# AIM2_-_GPS_REVB.net
KiCad netlist of a schematic drawn in Altium Designer
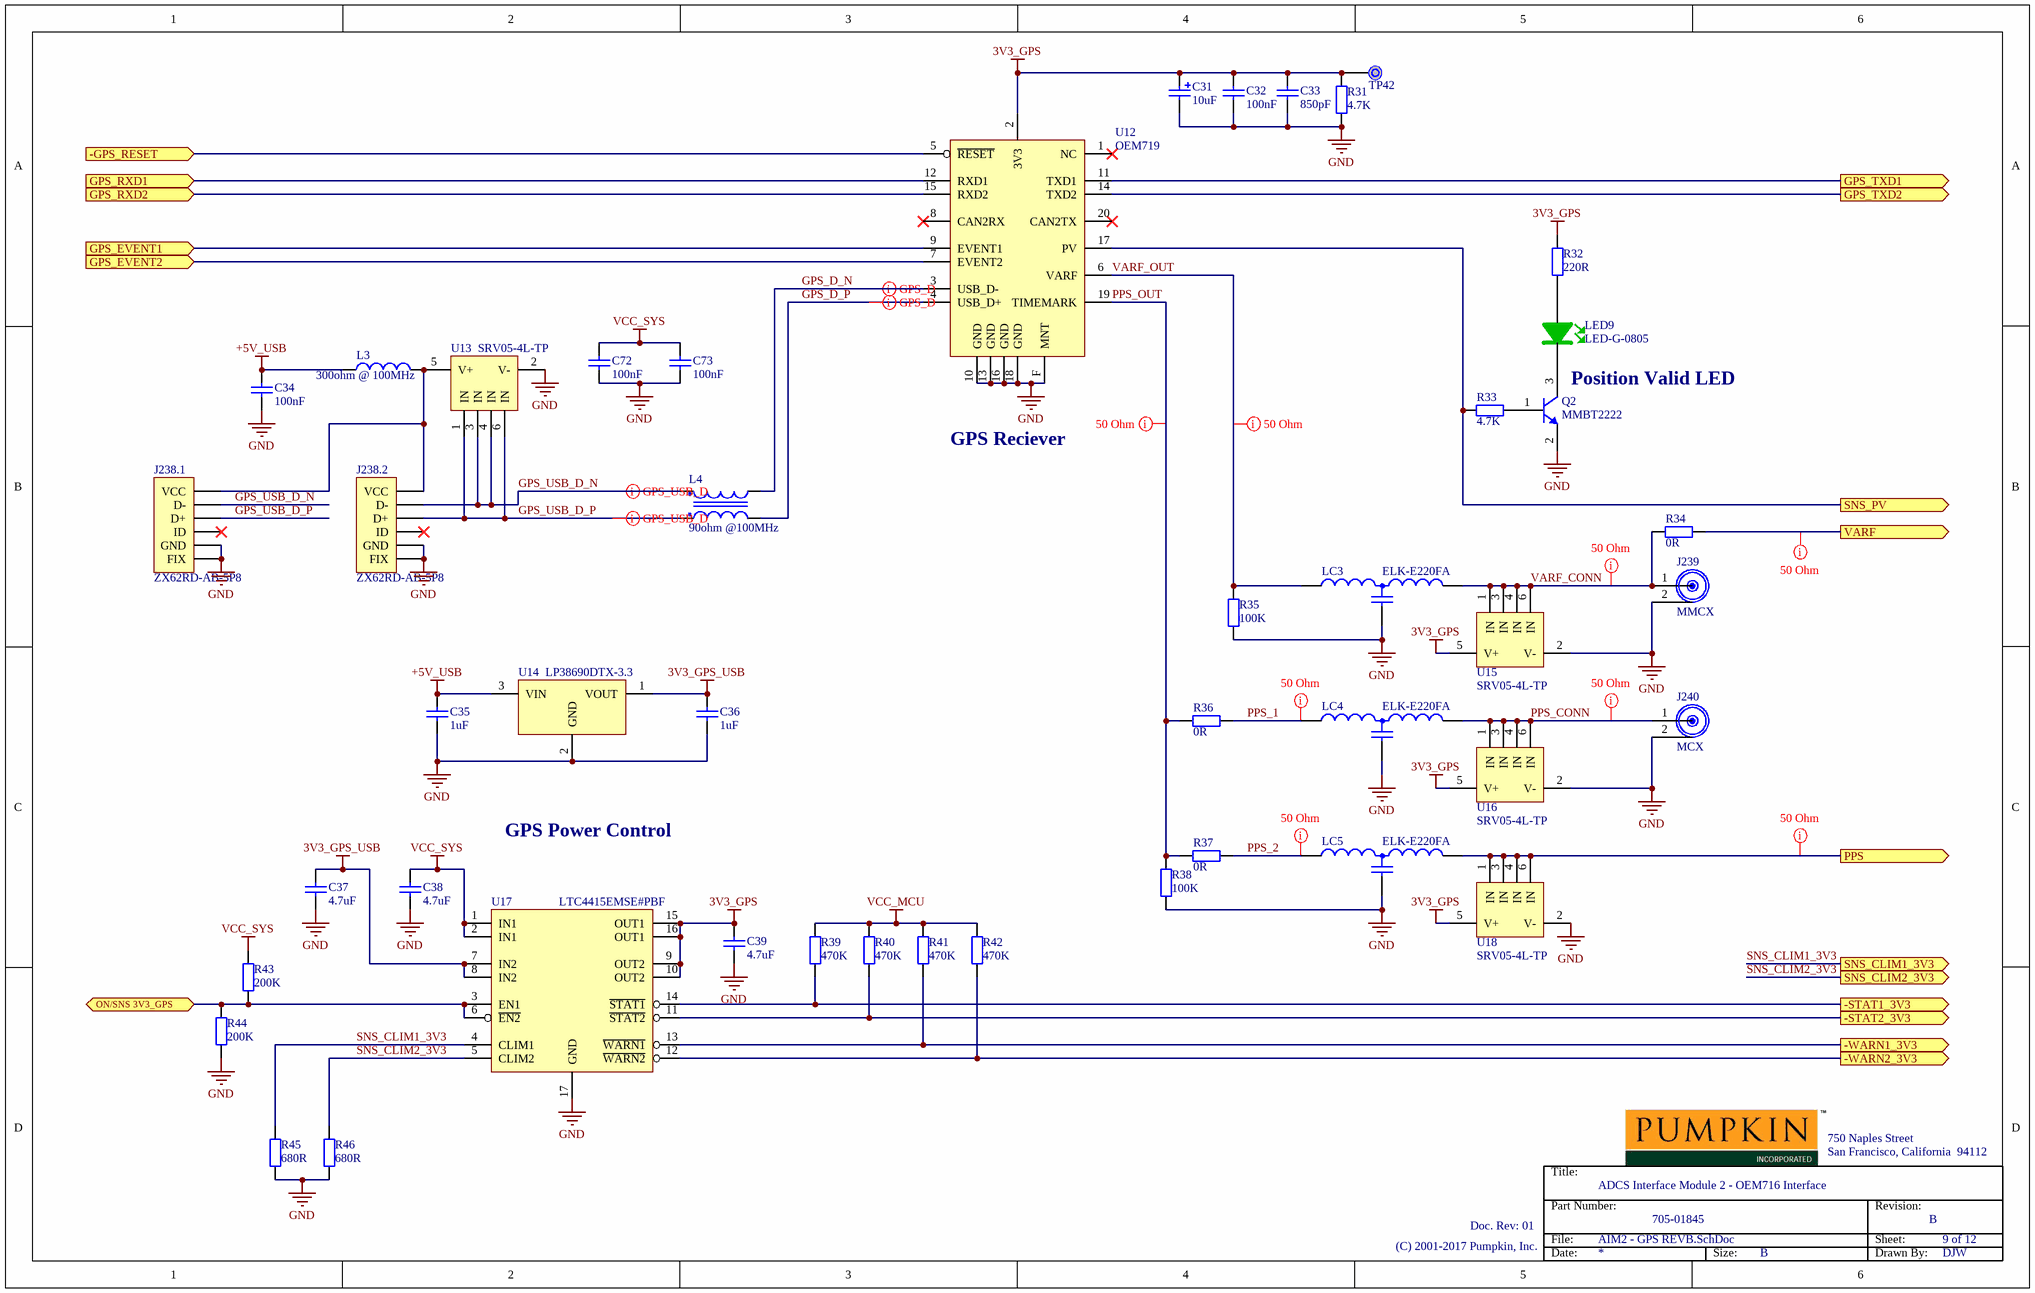
[diagram p0: AIM2 - GPS REVB.SchDoc]

(export (version "E")
  (design (tool "Eeschema 10.0.6"))
  (components
    (comp (ref "C31")
      (value "10uF")
      (footprint "6032 POLAR CAP")
      (description "Capacitor 10uF 6032 TANT 16V 10%")
      (libsource (lib "Supernova passives") (part "Capacitor 10uF 6032 Tantalum"))
    )
    (comp (ref "C32")
      (value "100nF")
      (footprint "0603 CAP")
      (description "Capacitor 100nF 0603 X7R 50V 5%")
      (libsource (lib "Supernova passives") (part "Capacitor 100nF 0603"))
    )
    (comp (ref "C33")
      (value "850pF")
      (footprint "0603 CAP")
      (description "Capacitor 850pF 0603 100V")
      (libsource (lib "Supernova passives") (part "Capacitor 850pF 0603"))
    )
    (comp (ref "C34")
      (value "100nF")
      (footprint "0603 CAP")
      (description "Capacitor 100nF 0603 X7R 50V 5%")
      (libsource (lib "Supernova passives") (part "Capacitor 100nF 0603"))
    )
    (comp (ref "C35")
      (value "1uF")
      (footprint "0805 CAP")
      (description "Capacitor 1uF 0805 X7R 25V 10%")
      (libsource (lib "Supernova passives") (part "Capacitor 1uF 0805"))
    )
    (comp (ref "C36")
      (value "1uF")
      (footprint "0805 CAP")
      (description "Capacitor 1uF 0805 X7R 25V 10%")
      (libsource (lib "Supernova passives") (part "Capacitor 1uF 0805"))
    )
    (comp (ref "C37")
      (value "4.7uF")
      (footprint "0805 CAP")
      (description "Capacitor 4.7uF 0805 X7R 35V 10%")
      (libsource (lib "Supernova passives") (part "Capacitor 4.7uF 0805"))
    )
    (comp (ref "C38")
      (value "4.7uF")
      (footprint "0805 CAP")
      (description "Capacitor 4.7uF 0805 X7R 35V 10%")
      (libsource (lib "Supernova passives") (part "Capacitor 4.7uF 0805"))
    )
    (comp (ref "C39")
      (value "4.7uF")
      (footprint "0805 CAP")
      (description "Capacitor 4.7uF 0805 X7R 35V 10%")
      (libsource (lib "Supernova passives") (part "Capacitor 4.7uF 0805"))
    )
    (comp (ref "C72")
      (value "100nF")
      (footprint "0603 CAP")
      (description "Capacitor 100nF 0603 X7R 50V 5%")
      (libsource (lib "Supernova passives") (part "Capacitor 100nF 0603"))
    )
    (comp (ref "C73")
      (value "100nF")
      (footprint "0603 CAP")
      (description "Capacitor 100nF 0603 X7R 50V 5%")
      (libsource (lib "Supernova passives") (part "Capacitor 100nF 0603"))
    )
    (comp (ref "J238.1")
      (value "ZX62RD-AB-5P8")
      (footprint "SM$5C$ZX62RD-AB-5P8")
      (description "Header USB Micro AB")
      (libsource (lib "Supernova") (part "ZX62RD-AB-5P8"))
    )
    (comp (ref "J238.2")
      (value "ZX62RD-AB-5P8")
      (footprint "SM$5C$ZX62RD-AB-5P8")
      (description "Header USB Micro AB")
      (libsource (lib "Supernova") (part "ZX62RD-AB-5P8"))
    )
    (comp (ref "J239")
      (value "MMCX")
      (footprint "mmcx")
      (description "Header MMCX Through-hole vertical")
      (libsource (lib "Supernova") (part "MMCX"))
    )
    (comp (ref "J240")
      (value "MCX")
      (footprint "MCX")
      (description "Header MCX Through-hole vertical")
      (libsource (lib "Supernova") (part "MCX"))
    )
    (comp (ref "L3")
      (value "300ohm @ 100MHz")
      (footprint "0603 IND")
      (description "Ferrite Bead 300ohm @ 100MHz")
      (libsource (lib "Supernova passives") (part "Ferrite Bead 300ohm @ 100MHz"))
    )
    (comp (ref "L4")
      (value "90ohm @100MHz")
      (footprint "DFN250P320X200-4N")
      (description "Choke Common-mode 90ohm @ 100MHz")
      (libsource (lib "Supernova passives") (part "Choke 90ohm @ 100MHz"))
    )
    (comp (ref "LC3")
      (value "ELK-E220FA")
      (footprint "ELK")
      (description "Filter LC 100MHz")
      (libsource (lib "Supernova passives") (part "LC Filter"))
    )
    (comp (ref "LC4")
      (value "ELK-E220FA")
      (footprint "ELK")
      (description "Filter LC 100MHz")
      (libsource (lib "Supernova passives") (part "LC Filter"))
    )
    (comp (ref "LC5")
      (value "ELK-E220FA")
      (footprint "ELK")
      (description "Filter LC 100MHz")
      (libsource (lib "Supernova passives") (part "LC Filter"))
    )
    (comp (ref "LED9")
      (value "LED-G-0805")
      (footprint "0805 LED-GREEN")
      (description "LED Green 0805")
      (libsource (lib "Supernova passives") (part "LED GREEN 0805"))
    )
    (comp (ref "Q2")
      (value "MMBT2222")
      (footprint "SOT23-3")
      (description "Transistor NPN")
      (libsource (lib "Supernova") (part "MMBT2222ALT1GOSCT-ND"))
    )
    (comp (ref "R31")
      (value "4.7K")
      (footprint "0805 RES")
      (description "Resistor 4.7K 0805 0.125W 1%")
      (libsource (lib "") (part "Resistor 4K7 0805_1"))
    )
    (comp (ref "R32")
      (value "220R")
      (footprint "0805 RES")
      (description "Resistor 220R 0805 0.125W 1%")
      (libsource (lib "Supernova passives") (part "Resistor 220R 0805"))
    )
    (comp (ref "R33")
      (value "4.7K")
      (footprint "0805 RES")
      (description "Resistor 4.7K 0805 0.125W 1%")
      (libsource (lib "Supernova passives") (part "Resistor 4K7 0805"))
    )
    (comp (ref "R34")
      (value "0R")
      (footprint "0805 RES")
      (description "Resistor 0R 0805 0.125W")
      (libsource (lib "Supernova passives") (part "Resistor 0R 0805"))
    )
    (comp (ref "R35")
      (value "100K")
      (footprint "0805 RES")
      (description "Resistor 100K 0805 0.5W 1%")
      (libsource (lib "Supernova passives") (part "Resistor 100K 0805"))
    )
    (comp (ref "R36")
      (value "0R")
      (footprint "0805 RES")
      (description "Resistor 0R 0805 0.125W")
      (libsource (lib "Supernova passives") (part "Resistor 0R 0805"))
    )
    (comp (ref "R37")
      (value "0R")
      (footprint "0805 RES")
      (description "Resistor 0R 0805 0.125W")
      (libsource (lib "Supernova passives") (part "Resistor 0R 0805"))
    )
    (comp (ref "R38")
      (value "100K")
      (footprint "0805 RES")
      (description "Resistor 100K 0805 0.5W 1%")
      (libsource (lib "Supernova passives") (part "Resistor 100K 0805"))
    )
    (comp (ref "R39")
      (value "470K")
      (footprint "0805 RES")
      (description "Resistor 470K 0805 0.125W 0.1%")
      (libsource (lib "Supernova passives") (part "Resistor 470K 0805"))
    )
    (comp (ref "R40")
      (value "470K")
      (footprint "0805 RES")
      (description "Resistor 470K 0805 0.125W 0.1%")
      (libsource (lib "Supernova passives") (part "Resistor 470K 0805"))
    )
    (comp (ref "R41")
      (value "470K")
      (footprint "0805 RES")
      (description "Resistor 470K 0805 0.125W 0.1%")
      (libsource (lib "Supernova passives") (part "Resistor 470K 0805"))
    )
    (comp (ref "R42")
      (value "470K")
      (footprint "0805 RES")
      (description "Resistor 470K 0805 0.125W 0.1%")
      (libsource (lib "Supernova passives") (part "Resistor 470K 0805"))
    )
    (comp (ref "R43")
      (value "200K")
      (footprint "0805 RES")
      (description "Resistor 200K 0805 0.125W 1%")
      (libsource (lib "Supernova passives") (part "Resistor 200K 0805"))
    )
    (comp (ref "R44")
      (value "200K")
      (footprint "0805 RES")
      (description "Resistor 200K 0805 0.125W 1%")
      (libsource (lib "Supernova passives") (part "Resistor 200K 0805"))
    )
    (comp (ref "R45")
      (value "680R")
      (footprint "0805 RES")
      (description "Resistor 470K 0805 0.125W 1%")
      (libsource (lib "Supernova passives") (part "Resistor 680R 0805"))
    )
    (comp (ref "R46")
      (value "680R")
      (footprint "0805 RES")
      (description "Resistor 470K 0805 0.125W 1%")
      (libsource (lib "Supernova passives") (part "Resistor 680R 0805"))
    )
    (comp (ref "TP42")
      (value "Testpoint")
      (footprint "Testpoint")
      (libsource (lib "Supernova") (part "Testpoint"))
    )
    (comp (ref "U12")
      (value "OEM719")
      (footprint "OEM719")
      (description "GPS Reciever")
      (libsource (lib "Supernova") (part "OEM719"))
    )
    (comp (ref "U13")
      (value "SRV05-4L-TP")
      (footprint "SOT23-6")
      (description "IC ESD protection 4 input")
      (libsource (lib "") (part "SRV05-4L-TP_1"))
    )
    (comp (ref "U14")
      (value "LP38690DTX-3.3")
      (footprint "DPAK")
      (description "Regulator 3.3V LDO")
      (libsource (lib "Supernova") (part "LP38690DTX-3.3"))
    )
    (comp (ref "U15")
      (value "SRV05-4L-TP")
      (footprint "SOT23-6")
      (description "IC ESD protection 4 input")
      (libsource (lib "Supernova") (part "SRV05-4L-TP"))
    )
    (comp (ref "U16")
      (value "SRV05-4L-TP")
      (footprint "SOT23-6")
      (description "IC ESD protection 4 input")
      (libsource (lib "Supernova") (part "SRV05-4L-TP"))
    )
    (comp (ref "U17")
      (value "LTC4415EMSE#PBF")
      (footprint "MSOP-16")
      (description "IC Driver Dual Idewal Diode")
      (libsource (lib "Supernova") (part "LTC4415"))
    )
    (comp (ref "U18")
      (value "SRV05-4L-TP")
      (footprint "SOT23-6")
      (description "IC ESD protection 4 input")
      (libsource (lib "Supernova") (part "SRV05-4L-TP"))
    )
  )
  (nets
    (net (code "1") (name "+5V_USB") (class "Default")
      (node (ref "C34") (pin "2") (pinfunction "2_2") (pintype "passive"))
      (node (ref "C35") (pin "2") (pinfunction "2_2") (pintype "passive"))
      (node (ref "L3") (pin "1") (pinfunction "1_1") (pintype "passive"))
      (node (ref "U14") (pin "3") (pinfunction "VIN_3") (pintype "passive"))
    )
    (net (code "2") (name "/-GPS_RESET") (class "Default")
      (node (ref "U12") (pin "5") (pinfunction "~{RESET}_5") (pintype "passive"))
    )
    (net (code "3") (name "/-STAT1_3V3") (class "Default")
      (node (ref "R39") (pin "1") (pinfunction "1_1") (pintype "passive"))
      (node (ref "U17") (pin "14") (pinfunction "~{STAT1}_14") (pintype "passive"))
    )
    (net (code "4") (name "/-STAT2_3V3") (class "Default")
      (node (ref "R40") (pin "1") (pinfunction "1_1") (pintype "passive"))
      (node (ref "U17") (pin "11") (pinfunction "~{STAT2}_11") (pintype "passive"))
    )
    (net (code "5") (name "/-WARN1_3V3") (class "Default")
      (node (ref "R41") (pin "1") (pinfunction "1_1") (pintype "passive"))
      (node (ref "U17") (pin "13") (pinfunction "~{WARN1}_13") (pintype "passive"))
    )
    (net (code "6") (name "/-WARN2_3V3") (class "Default")
      (node (ref "R42") (pin "1") (pinfunction "1_1") (pintype "passive"))
      (node (ref "U17") (pin "12") (pinfunction "~{WARN2}_12") (pintype "passive"))
    )
    (net (code "7") (name "/GPS_D_N") (class "Default")
      (node (ref "L4") (pin "2") (pinfunction "2_2") (pintype "passive"))
      (node (ref "U12") (pin "3") (pinfunction "USB_D-_3") (pintype "passive"))
    )
    (net (code "8") (name "/GPS_D_P") (class "Default")
      (node (ref "L4") (pin "3") (pinfunction "3_3") (pintype "passive"))
      (node (ref "U12") (pin "4") (pinfunction "USB_D+_4") (pintype "passive"))
    )
    (net (code "9") (name "/GPS_EVENT1") (class "Default")
      (node (ref "U12") (pin "9") (pinfunction "EVENT1_9") (pintype "passive"))
    )
    (net (code "10") (name "/GPS_EVENT2") (class "Default")
      (node (ref "U12") (pin "7") (pinfunction "EVENT2_7") (pintype "passive"))
    )
    (net (code "11") (name "/GPS_RXD1") (class "Default")
      (node (ref "U12") (pin "12") (pinfunction "RXD1_12") (pintype "passive"))
    )
    (net (code "12") (name "/GPS_RXD2") (class "Default")
      (node (ref "U12") (pin "15") (pinfunction "RXD2_15") (pintype "passive"))
    )
    (net (code "13") (name "/GPS_TXD1") (class "Default")
      (node (ref "U12") (pin "11") (pinfunction "TXD1_11") (pintype "passive"))
    )
    (net (code "14") (name "/GPS_TXD2") (class "Default")
      (node (ref "U12") (pin "14") (pinfunction "TXD2_14") (pintype "passive"))
    )
    (net (code "15") (name "/GPS_USB_D_N") (class "Default")
      (node (ref "J238.1") (pin "2") (pinfunction "D-_2") (pintype "passive"))
      (node (ref "J238.2") (pin "2") (pinfunction "D-_2") (pintype "passive"))
      (node (ref "L4") (pin "1") (pinfunction "1_1") (pintype "passive"))
      (node (ref "U13") (pin "3") (pinfunction "IN_3") (pintype "passive"))
      (node (ref "U13") (pin "4") (pinfunction "IN_4") (pintype "passive"))
    )
    (net (code "16") (name "/GPS_USB_D_P") (class "Default")
      (node (ref "J238.1") (pin "3") (pinfunction "D+_3") (pintype "passive"))
      (node (ref "J238.2") (pin "3") (pinfunction "D+_3") (pintype "passive"))
      (node (ref "L4") (pin "4") (pinfunction "4_4") (pintype "passive"))
      (node (ref "U13") (pin "1") (pinfunction "IN_1") (pintype "passive"))
      (node (ref "U13") (pin "6") (pinfunction "IN_6") (pintype "passive"))
    )
    (net (code "17") (name "/ON{slash}SNS 3V3_GPS") (class "Default")
      (node (ref "R43") (pin "1") (pinfunction "1_1") (pintype "passive"))
      (node (ref "R44") (pin "2") (pinfunction "2_2") (pintype "passive"))
      (node (ref "U17") (pin "3") (pinfunction "EN1_3") (pintype "passive"))
      (node (ref "U17") (pin "6") (pinfunction "~{EN2}_6") (pintype "passive"))
    )
    (net (code "18") (name "/PPS") (class "Default")
      (node (ref "LC5") (pin "3") (pinfunction "3_3") (pintype "passive"))
      (node (ref "U18") (pin "1") (pinfunction "IN_1") (pintype "passive"))
      (node (ref "U18") (pin "3") (pinfunction "IN_3") (pintype "passive"))
      (node (ref "U18") (pin "4") (pinfunction "IN_4") (pintype "passive"))
      (node (ref "U18") (pin "6") (pinfunction "IN_6") (pintype "passive"))
    )
    (net (code "19") (name "/PPS_1") (class "Default")
      (node (ref "LC4") (pin "1") (pinfunction "1_1") (pintype "passive"))
      (node (ref "R36") (pin "2") (pinfunction "2_2") (pintype "passive"))
    )
    (net (code "20") (name "/PPS_2") (class "Default")
      (node (ref "LC5") (pin "1") (pinfunction "1_1") (pintype "passive"))
      (node (ref "R37") (pin "2") (pinfunction "2_2") (pintype "passive"))
    )
    (net (code "21") (name "/PPS_CONN") (class "Default")
      (node (ref "J240") (pin "1") (pinfunction "7_1") (pintype "passive"))
      (node (ref "LC4") (pin "3") (pinfunction "3_3") (pintype "passive"))
      (node (ref "U16") (pin "1") (pinfunction "IN_1") (pintype "passive"))
      (node (ref "U16") (pin "3") (pinfunction "IN_3") (pintype "passive"))
      (node (ref "U16") (pin "4") (pinfunction "IN_4") (pintype "passive"))
      (node (ref "U16") (pin "6") (pinfunction "IN_6") (pintype "passive"))
    )
    (net (code "22") (name "/PPS_OUT") (class "Default")
      (node (ref "R36") (pin "1") (pinfunction "1_1") (pintype "passive"))
      (node (ref "R37") (pin "1") (pinfunction "1_1") (pintype "passive"))
      (node (ref "R38") (pin "2") (pinfunction "2_2") (pintype "passive"))
      (node (ref "U12") (pin "19") (pinfunction "TIMEMARK_19") (pintype "passive"))
    )
    (net (code "23") (name "/SNS_CLIM1_3V3") (class "Default")
      (node (ref "R45") (pin "2") (pinfunction "2_2") (pintype "passive"))
      (node (ref "U17") (pin "4") (pinfunction "CLIM1_4") (pintype "passive"))
    )
    (net (code "24") (name "/SNS_CLIM2_3V3") (class "Default")
      (node (ref "R46") (pin "2") (pinfunction "2_2") (pintype "passive"))
      (node (ref "U17") (pin "5") (pinfunction "CLIM2_5") (pintype "passive"))
    )
    (net (code "25") (name "/SNS_PV") (class "Default")
      (node (ref "R33") (pin "1") (pinfunction "1_1") (pintype "passive"))
      (node (ref "U12") (pin "17") (pinfunction "PV_17") (pintype "passive"))
    )
    (net (code "26") (name "/VARF") (class "Default")
      (node (ref "R34") (pin "2") (pinfunction "2_2") (pintype "passive"))
    )
    (net (code "27") (name "/VARF_CONN") (class "Default")
      (node (ref "J239") (pin "1") (pinfunction "7_1") (pintype "passive"))
      (node (ref "LC3") (pin "3") (pinfunction "3_3") (pintype "passive"))
      (node (ref "R34") (pin "1") (pinfunction "1_1") (pintype "passive"))
      (node (ref "U15") (pin "1") (pinfunction "IN_1") (pintype "passive"))
      (node (ref "U15") (pin "3") (pinfunction "IN_3") (pintype "passive"))
      (node (ref "U15") (pin "4") (pinfunction "IN_4") (pintype "passive"))
      (node (ref "U15") (pin "6") (pinfunction "IN_6") (pintype "passive"))
    )
    (net (code "28") (name "/VARF_OUT") (class "Default")
      (node (ref "LC3") (pin "1") (pinfunction "1_1") (pintype "passive"))
      (node (ref "R35") (pin "2") (pinfunction "2_2") (pintype "passive"))
      (node (ref "U12") (pin "6") (pinfunction "VARF_6") (pintype "passive"))
    )
    (net (code "29") (name "3V3_GPS") (class "Default")
      (node (ref "C31") (pin "1") (pinfunction "1_1") (pintype "passive"))
      (node (ref "C32") (pin "2") (pinfunction "2_2") (pintype "passive"))
      (node (ref "C33") (pin "2") (pinfunction "2_2") (pintype "passive"))
      (node (ref "C39") (pin "2") (pinfunction "2_2") (pintype "passive"))
      (node (ref "R31") (pin "2") (pinfunction "2_2") (pintype "passive"))
      (node (ref "R32") (pin "2") (pinfunction "2_2") (pintype "passive"))
      (node (ref "TP42") (pin "1") (pinfunction "1_1") (pintype "passive"))
      (node (ref "U12") (pin "2") (pinfunction "3V3_2") (pintype "passive"))
      (node (ref "U15") (pin "5") (pinfunction "V+_5") (pintype "passive"))
      (node (ref "U16") (pin "5") (pinfunction "V+_5") (pintype "passive"))
      (node (ref "U17") (pin "10") (pinfunction "OUT2_10") (pintype "passive"))
      (node (ref "U17") (pin "15") (pinfunction "OUT1_15") (pintype "passive"))
      (node (ref "U17") (pin "16") (pinfunction "OUT1_16") (pintype "passive"))
      (node (ref "U17") (pin "9") (pinfunction "OUT2_9") (pintype "passive"))
      (node (ref "U18") (pin "5") (pinfunction "V+_5") (pintype "passive"))
    )
    (net (code "30") (name "3V3_GPS_USB") (class "Default")
      (node (ref "C36") (pin "2") (pinfunction "2_2") (pintype "passive"))
      (node (ref "C37") (pin "2") (pinfunction "2_2") (pintype "passive"))
      (node (ref "U14") (pin "1") (pinfunction "VOUT_1") (pintype "passive"))
      (node (ref "U17") (pin "7") (pinfunction "IN2_7") (pintype "passive"))
      (node (ref "U17") (pin "8") (pinfunction "IN2_8") (pintype "passive"))
    )
    (net (code "31") (name "GND") (class "Default")
      (node (ref "C31") (pin "2") (pinfunction "2_2") (pintype "passive"))
      (node (ref "C32") (pin "1") (pinfunction "1_1") (pintype "passive"))
      (node (ref "C33") (pin "1") (pinfunction "1_1") (pintype "passive"))
      (node (ref "C34") (pin "1") (pinfunction "1_1") (pintype "passive"))
      (node (ref "C35") (pin "1") (pinfunction "1_1") (pintype "passive"))
      (node (ref "C36") (pin "1") (pinfunction "1_1") (pintype "passive"))
      (node (ref "C37") (pin "1") (pinfunction "1_1") (pintype "passive"))
      (node (ref "C38") (pin "1") (pinfunction "1_1") (pintype "passive"))
      (node (ref "C39") (pin "1") (pinfunction "1_1") (pintype "passive"))
      (node (ref "C72") (pin "1") (pinfunction "1_1") (pintype "passive"))
      (node (ref "C73") (pin "1") (pinfunction "1_1") (pintype "passive"))
      (node (ref "J238.1") (pin "5") (pinfunction "GND_5") (pintype "passive"))
      (node (ref "J238.1") (pin "F") (pinfunction "FIX_F") (pintype "passive"))
      (node (ref "J238.2") (pin "5") (pinfunction "GND_5") (pintype "passive"))
      (node (ref "J238.2") (pin "F") (pinfunction "FIX_F") (pintype "passive"))
      (node (ref "J239") (pin "2") (pinfunction "7_2") (pintype "passive"))
      (node (ref "J240") (pin "2") (pinfunction "7_2") (pintype "passive"))
      (node (ref "LC3") (pin "2") (pinfunction "2_2") (pintype "passive"))
      (node (ref "LC4") (pin "2") (pinfunction "2_2") (pintype "passive"))
      (node (ref "LC5") (pin "2") (pinfunction "2_2") (pintype "passive"))
      (node (ref "Q2") (pin "2") (pinfunction "E_2") (pintype "passive"))
      (node (ref "R31") (pin "1") (pinfunction "1_1") (pintype "passive"))
      (node (ref "R35") (pin "1") (pinfunction "1_1") (pintype "passive"))
      (node (ref "R38") (pin "1") (pinfunction "1_1") (pintype "passive"))
      (node (ref "R44") (pin "1") (pinfunction "1_1") (pintype "passive"))
      (node (ref "R45") (pin "1") (pinfunction "1_1") (pintype "passive"))
      (node (ref "R46") (pin "1") (pinfunction "1_1") (pintype "passive"))
      (node (ref "U12") (pin "10") (pinfunction "GND_10") (pintype "passive"))
      (node (ref "U12") (pin "13") (pinfunction "GND_13") (pintype "passive"))
      (node (ref "U12") (pin "16") (pinfunction "GND_16") (pintype "passive"))
      (node (ref "U12") (pin "18") (pinfunction "GND_18") (pintype "passive"))
      (node (ref "U12") (pin "F") (pinfunction "MNT_F") (pintype "passive"))
      (node (ref "U13") (pin "2") (pinfunction "V-_2") (pintype "passive"))
      (node (ref "U14") (pin "2") (pinfunction "GND_2") (pintype "passive"))
      (node (ref "U15") (pin "2") (pinfunction "V-_2") (pintype "passive"))
      (node (ref "U16") (pin "2") (pinfunction "V-_2") (pintype "passive"))
      (node (ref "U17") (pin "17") (pinfunction "GND_17") (pintype "passive"))
      (node (ref "U18") (pin "2") (pinfunction "V-_2") (pintype "passive"))
    )
    (net (code "32") (name "Net-(J238.1-VCC)") (class "Default")
      (node (ref "J238.1") (pin "1") (pinfunction "VCC_1") (pintype "passive"))
      (node (ref "J238.2") (pin "1") (pinfunction "VCC_1") (pintype "passive"))
      (node (ref "L3") (pin "2") (pinfunction "2_2") (pintype "passive"))
      (node (ref "U13") (pin "5") (pinfunction "V+_5") (pintype "passive"))
    )
    (net (code "33") (name "Net-(LED9-Pad2)") (class "Default")
      (node (ref "LED9") (pin "2") (pinfunction "2_2") (pintype "passive"))
      (node (ref "R32") (pin "1") (pinfunction "1_1") (pintype "passive"))
    )
    (net (code "34") (name "Net-(Q2-B)") (class "Default")
      (node (ref "Q2") (pin "1") (pinfunction "B_1") (pintype "passive"))
      (node (ref "R33") (pin "2") (pinfunction "2_2") (pintype "passive"))
    )
    (net (code "35") (name "Net-(Q2-C)") (class "Default")
      (node (ref "LED9") (pin "1") (pinfunction "1_1") (pintype "passive"))
      (node (ref "Q2") (pin "3") (pinfunction "C_3") (pintype "passive"))
    )
    (net (code "36") (name "VCC_MCU") (class "Default")
      (node (ref "R39") (pin "2") (pinfunction "2_2") (pintype "passive"))
      (node (ref "R40") (pin "2") (pinfunction "2_2") (pintype "passive"))
      (node (ref "R41") (pin "2") (pinfunction "2_2") (pintype "passive"))
      (node (ref "R42") (pin "2") (pinfunction "2_2") (pintype "passive"))
    )
    (net (code "37") (name "VCC_SYS") (class "Default")
      (node (ref "C38") (pin "2") (pinfunction "2_2") (pintype "passive"))
      (node (ref "C72") (pin "2") (pinfunction "2_2") (pintype "passive"))
      (node (ref "C73") (pin "2") (pinfunction "2_2") (pintype "passive"))
      (node (ref "R43") (pin "2") (pinfunction "2_2") (pintype "passive"))
      (node (ref "U17") (pin "1") (pinfunction "IN1_1") (pintype "passive"))
      (node (ref "U17") (pin "2") (pinfunction "IN1_2") (pintype "passive"))
    )
    (net (code "38") (name "unconnected-(J238.1-ID-Pad4)") (class "Default")
      (node (ref "J238.1") (pin "4") (pinfunction "ID_4") (pintype "passive+no_connect"))
    )
    (net (code "39") (name "unconnected-(J238.2-ID-Pad4)") (class "Default")
      (node (ref "J238.2") (pin "4") (pinfunction "ID_4") (pintype "passive+no_connect"))
    )
    (net (code "40") (name "unconnected-(U12-CAN2RX-Pad8)") (class "Default")
      (node (ref "U12") (pin "8") (pinfunction "CAN2RX_8") (pintype "passive+no_connect"))
    )
    (net (code "41") (name "unconnected-(U12-CAN2TX-Pad20)") (class "Default")
      (node (ref "U12") (pin "20") (pinfunction "CAN2TX_20") (pintype "passive+no_connect"))
    )
    (net (code "42") (name "unconnected-(U12-NC-Pad1)") (class "Default")
      (node (ref "U12") (pin "1") (pinfunction "NC_1") (pintype "passive+no_connect"))
    )
  )
)
